# prg-flash.net
KiCad netlist of a schematic drawn in Altium Designer
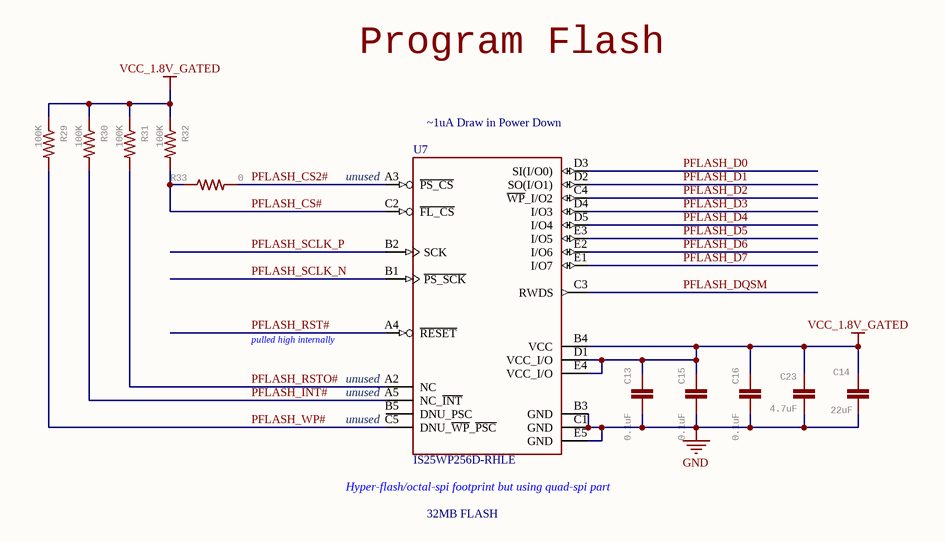
[diagram p0: prg-flash.SchDoc]

(export (version "E")
  (design (tool "Eeschema 10.0.6"))
  (components
    (comp (ref "C13")
      (value "0.1uF")
      (footprint "0402-CAP")
      (description "CAPACITOR, European symbol")
      (fields (field (name "MPN") "C0402C104Z4VAC"))
      (libsource (lib "openmv-ae3") (part "C-EUC0201"))
    )
    (comp (ref "C14")
      (value "22uF")
      (footprint "0805")
      (fields (field (name "MPN") "CL21A226MQQNNNE"))
      (libsource (lib "openmv-ae3") (part "22UF-0805-6.3V-20%"))
    )
    (comp (ref "C15")
      (value "0.1uF")
      (footprint "0402-CAP")
      (description "CAPACITOR, European symbol")
      (fields (field (name "MPN") "C0402C104Z4VAC"))
      (libsource (lib "openmv-ae3") (part "C-EUC0201"))
    )
    (comp (ref "C16")
      (value "0.1uF")
      (footprint "0402-CAP")
      (description "CAPACITOR, European symbol")
      (fields (field (name "MPN") "C0402C104Z4VAC"))
      (libsource (lib "openmv-ae3") (part "C-EUC0201"))
    )
    (comp (ref "C23")
      (value "4.7uF")
      (footprint "0402-CAP")
      (description "CapacitorStandard 0603 ceramic capacitor, and 0.1\" leaded capacitor.")
      (fields (field (name "MPN") "JMK105BBJ475MV-F") (field (name "LIBRARYNAME") "sfe"))
      (libsource (lib "openmv-ae3") (part "CAP0402-CAP"))
    )
    (comp (ref "R29")
      (value "100K")
      (footprint "0402-RES")
      (description "ResistorBasic schematic elements and footprints for 0603, 1206, and PTH resistors.")
      (fields (field (name "MPN") "AC0402FR-07100KL") (field (name "LIBRARYNAME") "sfe"))
      (libsource (lib "openmv-ae3") (part "RESISTOR0402-RES"))
    )
    (comp (ref "R30")
      (value "100K")
      (footprint "0402-RES")
      (description "ResistorBasic schematic elements and footprints for 0603, 1206, and PTH resistors.")
      (fields (field (name "MPN") "AC0402FR-07100KL") (field (name "LIBRARYNAME") "sfe"))
      (libsource (lib "openmv-ae3") (part "RESISTOR0402-RES"))
    )
    (comp (ref "R31")
      (value "100K")
      (footprint "0402-RES")
      (description "ResistorBasic schematic elements and footprints for 0603, 1206, and PTH resistors.")
      (fields (field (name "MPN") "AC0402FR-07100KL") (field (name "LIBRARYNAME") "sfe"))
      (libsource (lib "openmv-ae3") (part "RESISTOR0402-RES"))
    )
    (comp (ref "R32")
      (value "100K")
      (footprint "0402-RES")
      (description "ResistorBasic schematic elements and footprints for 0603, 1206, and PTH resistors.")
      (fields (field (name "MPN") "AC0402FR-07100KL") (field (name "LIBRARYNAME") "sfe"))
      (libsource (lib "openmv-ae3") (part "RESISTOR0402-RES"))
    )
    (comp (ref "R33")
      (value "0")
      (footprint "0402-RES")
      (description "ResistorBasic schematic elements and footprints for 0603, 1206, and PTH resistors.")
      (fields (field (name "MPN") "RC0402JR-070R") (field (name "LIBRARYNAME") "sfe"))
      (libsource (lib "openmv-ae3") (part "RESISTOR0402-RES"))
    )
    (comp (ref "U7")
      (value "IS25WP256D-RHLE")
      (footprint "24-TBGA")
      (description "IC, Flash,32MB x 8, Octal SPI, Ind Temp, 1.8V,24-BGA")
      (fields (field (name "MF") "ISSI") (field (name "MPN") "IS25WP256D-RHLE"))
      (libsource (lib "openmv-ae3") (part "IS25WX256-JHLE"))
    )
  )
  (nets
    (net (code "1") (name "/PFLASH_CS#") (class "Default")
      (node (ref "R32") (pin "2") (pinfunction "2_2") (pintype "passive"))
      (node (ref "R33") (pin "1") (pinfunction "1_1") (pintype "passive"))
      (node (ref "U7") (pin "C2") (pinfunction "~{FL_CS}_C2") (pintype "input"))
    )
    (net (code "2") (name "/PFLASH_CS2#") (class "Default")
      (node (ref "R33") (pin "2") (pinfunction "2_2") (pintype "passive"))
      (node (ref "U7") (pin "A3") (pinfunction "~{PS_CS}_A3") (pintype "input"))
    )
    (net (code "3") (name "/PFLASH_D0") (class "Default")
      (node (ref "U7") (pin "D3") (pinfunction "SI(I/O0)_D3") (pintype "bidirectional"))
    )
    (net (code "4") (name "/PFLASH_D1") (class "Default")
      (node (ref "U7") (pin "D2") (pinfunction "SO(I/O1)_D2") (pintype "bidirectional"))
    )
    (net (code "5") (name "/PFLASH_D2") (class "Default")
      (node (ref "U7") (pin "C4") (pinfunction "~{WP}_I/O2_C4") (pintype "bidirectional"))
    )
    (net (code "6") (name "/PFLASH_D3") (class "Default")
      (node (ref "U7") (pin "D4") (pinfunction "I/O3_D4") (pintype "bidirectional"))
    )
    (net (code "7") (name "/PFLASH_D4") (class "Default")
      (node (ref "U7") (pin "D5") (pinfunction "I/O4_D5") (pintype "bidirectional"))
    )
    (net (code "8") (name "/PFLASH_D5") (class "Default")
      (node (ref "U7") (pin "E3") (pinfunction "I/O5_E3") (pintype "bidirectional"))
    )
    (net (code "9") (name "/PFLASH_D6") (class "Default")
      (node (ref "U7") (pin "E2") (pinfunction "I/O6_E2") (pintype "bidirectional"))
    )
    (net (code "10") (name "/PFLASH_D7") (class "Default")
      (node (ref "U7") (pin "E1") (pinfunction "I/O7_E1") (pintype "bidirectional"))
    )
    (net (code "11") (name "/PFLASH_DQSM") (class "Default")
      (node (ref "U7") (pin "C3") (pinfunction "RWDS_C3") (pintype "output"))
    )
    (net (code "12") (name "/PFLASH_INT#") (class "Default")
      (node (ref "R30") (pin "2") (pinfunction "2_2") (pintype "passive"))
      (node (ref "U7") (pin "A5") (pinfunction "NC_~{INT}_A5") (pintype "passive"))
    )
    (net (code "13") (name "/PFLASH_RST#") (class "Default")
      (node (ref "U7") (pin "A4") (pinfunction "~{RESET}_A4") (pintype "input"))
    )
    (net (code "14") (name "/PFLASH_RSTO#") (class "Default")
      (node (ref "R31") (pin "2") (pinfunction "2_2") (pintype "passive"))
      (node (ref "U7") (pin "A2") (pinfunction "NC_A2") (pintype "passive"))
    )
    (net (code "15") (name "/PFLASH_SCLK_N") (class "Default")
      (node (ref "U7") (pin "B1") (pinfunction "~{PS_SCK}_B1") (pintype "input"))
    )
    (net (code "16") (name "/PFLASH_SCLK_P") (class "Default")
      (node (ref "U7") (pin "B2") (pinfunction "SCK_B2") (pintype "input"))
    )
    (net (code "17") (name "/PFLASH_WP#") (class "Default")
      (node (ref "R29") (pin "2") (pinfunction "2_2") (pintype "passive"))
      (node (ref "U7") (pin "C5") (pinfunction "DNU_~{WP}_~{PSC}_C5") (pintype "passive"))
    )
    (net (code "18") (name "GND") (class "Default")
      (node (ref "C13") (pin "2") (pinfunction "2_2") (pintype "passive"))
      (node (ref "C14") (pin "1") (pinfunction "1_1") (pintype "passive"))
      (node (ref "C15") (pin "2") (pinfunction "2_2") (pintype "passive"))
      (node (ref "C16") (pin "2") (pinfunction "2_2") (pintype "passive"))
      (node (ref "C23") (pin "1") (pinfunction "1_1") (pintype "passive"))
      (node (ref "U7") (pin "B3") (pinfunction "GND_B3") (pintype "power_in"))
      (node (ref "U7") (pin "C1") (pinfunction "GND_C1") (pintype "power_in"))
      (node (ref "U7") (pin "E5") (pinfunction "GND_E5") (pintype "power_in"))
    )
    (net (code "19") (name "VCC_1.8V_GATED") (class "Default")
      (node (ref "C13") (pin "1") (pinfunction "1_1") (pintype "passive"))
      (node (ref "C14") (pin "2") (pinfunction "2_2") (pintype "passive"))
      (node (ref "C15") (pin "1") (pinfunction "1_1") (pintype "passive"))
      (node (ref "C16") (pin "1") (pinfunction "1_1") (pintype "passive"))
      (node (ref "C23") (pin "2") (pinfunction "2_2") (pintype "passive"))
      (node (ref "R29") (pin "1") (pinfunction "1_1") (pintype "passive"))
      (node (ref "R30") (pin "1") (pinfunction "1_1") (pintype "passive"))
      (node (ref "R31") (pin "1") (pinfunction "1_1") (pintype "passive"))
      (node (ref "R32") (pin "1") (pinfunction "1_1") (pintype "passive"))
      (node (ref "U7") (pin "B4") (pinfunction "VCC_B4") (pintype "power_in"))
      (node (ref "U7") (pin "D1") (pinfunction "VCC_I/O_D1") (pintype "power_in"))
      (node (ref "U7") (pin "E4") (pinfunction "VCC_I/O_E4") (pintype "power_in"))
    )
    (net (code "20") (name "unconnected-(U7-DNU_PSC-PadB5)") (class "Default")
      (node (ref "U7") (pin "B5") (pinfunction "DNU_PSC_B5") (pintype "passive"))
    )
  )
)
